# connect.net
KiCad netlist of a schematic drawn in Altium Designer
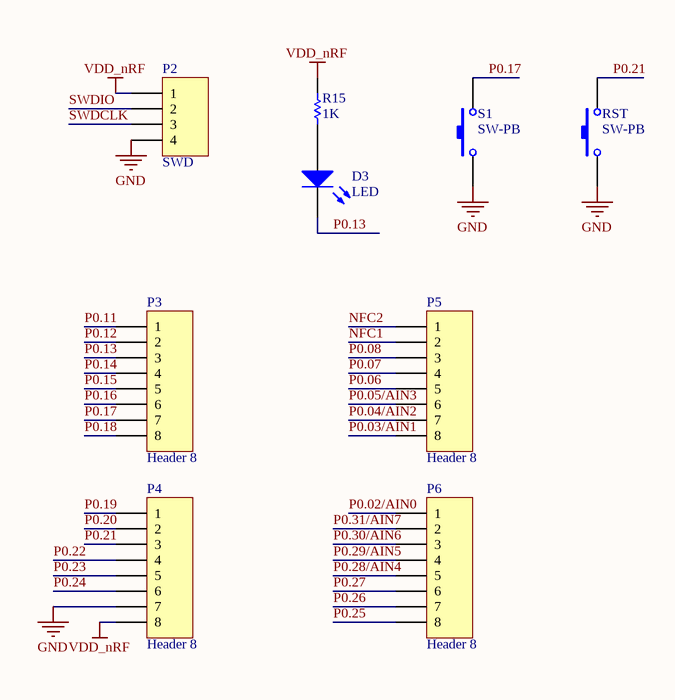
[diagram p0: connect.SchDoc]

(export (version "E")
  (design (tool "Eeschema 10.0.6"))
  (components
    (comp (ref "D3")
      (value "LED")
      (footprint "0603")
      (description "Typical INFRARED GaAs LED")
      (fields (field (name "PUBLISHER") "Altium Limited"))
      (libsource (lib "Mylibrary") (part "LED"))
    )
    (comp (ref "P2")
      (value "SWD")
      (footprint "HDR1X4")
      (description "Header, 4-Pin")
      (fields (field (name "PUBLISHER") "Altium Limited"))
      (libsource (lib "Miscellaneous Connectors") (part "Header 4"))
    )
    (comp (ref "P3")
      (value "Header 8")
      (footprint "HDR1X8")
      (description "Header, 8-Pin")
      (fields (field (name "PUBLISHER") "Altium Limited"))
      (libsource (lib "Miscellaneous Connectors") (part "Header 8"))
    )
    (comp (ref "P4")
      (value "Header 8")
      (footprint "HDR1X8")
      (description "Header, 8-Pin")
      (fields (field (name "PUBLISHER") "Altium Limited"))
      (libsource (lib "Miscellaneous Connectors") (part "Header 8"))
    )
    (comp (ref "P5")
      (value "Header 8")
      (footprint "HDR1X8")
      (description "Header, 8-Pin")
      (fields (field (name "PUBLISHER") "Altium Limited"))
      (libsource (lib "Miscellaneous Connectors") (part "Header 8"))
    )
    (comp (ref "P6")
      (value "Header 8")
      (footprint "HDR1X8")
      (description "Header, 8-Pin")
      (fields (field (name "PUBLISHER") "Altium Limited"))
      (libsource (lib "Miscellaneous Connectors") (part "Header 8"))
    )
    (comp (ref "R15")
      (value "1K")
      (footprint "R0603-M")
      (description "Resistor")
      (fields (field (name "Comment") "Resistors SMD"))
      (libsource (lib "Mylibrary") (part "Resistors SMD"))
    )
    (comp (ref "RST")
      (value "SW-PB")
      (footprint "SWITCH_SMD_4x3_DHT-1185")
      (description "Switch")
      (fields (field (name "PUBLISHER") "Altium Limited"))
      (libsource (lib "Mylibrary") (part "SW-PB"))
    )
    (comp (ref "S1")
      (value "SW-PB")
      (footprint "SWITCH_SMD_4x3_DHT-1185")
      (description "Switch")
      (fields (field (name "PUBLISHER") "Altium Limited"))
      (libsource (lib "Mylibrary") (part "SW-PB"))
    )
  )
  (nets
    (net (code "1") (name "/NFC1") (class "Default")
      (node (ref "P5") (pin "2") (pinfunction "2_2") (pintype "passive"))
    )
    (net (code "2") (name "/NFC2") (class "Default")
      (node (ref "P5") (pin "1") (pinfunction "1_1") (pintype "passive"))
    )
    (net (code "3") (name "/P0.02{slash}AIN0") (class "Default")
      (node (ref "P6") (pin "1") (pinfunction "1_1") (pintype "passive"))
    )
    (net (code "4") (name "/P0.03{slash}AIN1") (class "Default")
      (node (ref "P5") (pin "8") (pinfunction "8_8") (pintype "passive"))
    )
    (net (code "5") (name "/P0.04{slash}AIN2") (class "Default")
      (node (ref "P5") (pin "7") (pinfunction "7_7") (pintype "passive"))
    )
    (net (code "6") (name "/P0.05{slash}AIN3") (class "Default")
      (node (ref "P5") (pin "6") (pinfunction "6_6") (pintype "passive"))
    )
    (net (code "7") (name "/P0.06") (class "Default")
      (node (ref "P5") (pin "5") (pinfunction "5_5") (pintype "passive"))
    )
    (net (code "8") (name "/P0.07") (class "Default")
      (node (ref "P5") (pin "4") (pinfunction "4_4") (pintype "passive"))
    )
    (net (code "9") (name "/P0.08") (class "Default")
      (node (ref "P5") (pin "3") (pinfunction "3_3") (pintype "passive"))
    )
    (net (code "10") (name "/P0.11") (class "Default")
      (node (ref "P3") (pin "1") (pinfunction "1_1") (pintype "passive"))
    )
    (net (code "11") (name "/P0.12") (class "Default")
      (node (ref "P3") (pin "2") (pinfunction "2_2") (pintype "passive"))
    )
    (net (code "12") (name "/P0.13") (class "Default")
      (node (ref "D3") (pin "2") (pinfunction "K_2") (pintype "passive"))
      (node (ref "P3") (pin "3") (pinfunction "3_3") (pintype "passive"))
    )
    (net (code "13") (name "/P0.14") (class "Default")
      (node (ref "P3") (pin "4") (pinfunction "4_4") (pintype "passive"))
    )
    (net (code "14") (name "/P0.15") (class "Default")
      (node (ref "P3") (pin "5") (pinfunction "5_5") (pintype "passive"))
    )
    (net (code "15") (name "/P0.16") (class "Default")
      (node (ref "P3") (pin "6") (pinfunction "6_6") (pintype "passive"))
    )
    (net (code "16") (name "/P0.17") (class "Default")
      (node (ref "P3") (pin "7") (pinfunction "7_7") (pintype "passive"))
      (node (ref "S1") (pin "2") (pinfunction "2_2") (pintype "passive"))
    )
    (net (code "17") (name "/P0.18") (class "Default")
      (node (ref "P3") (pin "8") (pinfunction "8_8") (pintype "passive"))
    )
    (net (code "18") (name "/P0.19") (class "Default")
      (node (ref "P4") (pin "1") (pinfunction "1_1") (pintype "passive"))
    )
    (net (code "19") (name "/P0.20") (class "Default")
      (node (ref "P4") (pin "2") (pinfunction "2_2") (pintype "passive"))
    )
    (net (code "20") (name "/P0.21") (class "Default")
      (node (ref "P4") (pin "3") (pinfunction "3_3") (pintype "passive"))
      (node (ref "RST") (pin "2") (pinfunction "2_2") (pintype "passive"))
    )
    (net (code "21") (name "/P0.22") (class "Default")
      (node (ref "P4") (pin "4") (pinfunction "4_4") (pintype "passive"))
    )
    (net (code "22") (name "/P0.23") (class "Default")
      (node (ref "P4") (pin "5") (pinfunction "5_5") (pintype "passive"))
    )
    (net (code "23") (name "/P0.24") (class "Default")
      (node (ref "P4") (pin "6") (pinfunction "6_6") (pintype "passive"))
    )
    (net (code "24") (name "/P0.25") (class "Default")
      (node (ref "P6") (pin "8") (pinfunction "8_8") (pintype "passive"))
    )
    (net (code "25") (name "/P0.26") (class "Default")
      (node (ref "P6") (pin "7") (pinfunction "7_7") (pintype "passive"))
    )
    (net (code "26") (name "/P0.27") (class "Default")
      (node (ref "P6") (pin "6") (pinfunction "6_6") (pintype "passive"))
    )
    (net (code "27") (name "/P0.28{slash}AIN4") (class "Default")
      (node (ref "P6") (pin "5") (pinfunction "5_5") (pintype "passive"))
    )
    (net (code "28") (name "/P0.29{slash}AIN5") (class "Default")
      (node (ref "P6") (pin "4") (pinfunction "4_4") (pintype "passive"))
    )
    (net (code "29") (name "/P0.30{slash}AIN6") (class "Default")
      (node (ref "P6") (pin "3") (pinfunction "3_3") (pintype "passive"))
    )
    (net (code "30") (name "/P0.31{slash}AIN7") (class "Default")
      (node (ref "P6") (pin "2") (pinfunction "2_2") (pintype "passive"))
    )
    (net (code "31") (name "/SWDCLK") (class "Default")
      (node (ref "P2") (pin "3") (pinfunction "3_3") (pintype "passive"))
    )
    (net (code "32") (name "/SWDIO") (class "Default")
      (node (ref "P2") (pin "2") (pinfunction "2_2") (pintype "passive"))
    )
    (net (code "33") (name "GND") (class "Default")
      (node (ref "P2") (pin "4") (pinfunction "4_4") (pintype "passive"))
      (node (ref "P4") (pin "7") (pinfunction "7_7") (pintype "passive"))
      (node (ref "RST") (pin "1") (pinfunction "1_1") (pintype "passive"))
      (node (ref "S1") (pin "1") (pinfunction "1_1") (pintype "passive"))
    )
    (net (code "34") (name "Net-(D3-A)") (class "Default")
      (node (ref "D3") (pin "1") (pinfunction "A_1") (pintype "passive"))
      (node (ref "R15") (pin "2") (pinfunction "2_2") (pintype "passive"))
    )
    (net (code "35") (name "VDD_nRF") (class "Default")
      (node (ref "P2") (pin "1") (pinfunction "1_1") (pintype "passive"))
      (node (ref "P4") (pin "8") (pinfunction "8_8") (pintype "passive"))
      (node (ref "R15") (pin "1") (pinfunction "1_1") (pintype "passive"))
    )
  )
)
